# tenacity_pcb.net
KiCad netlist of a schematic drawn in EAGLE
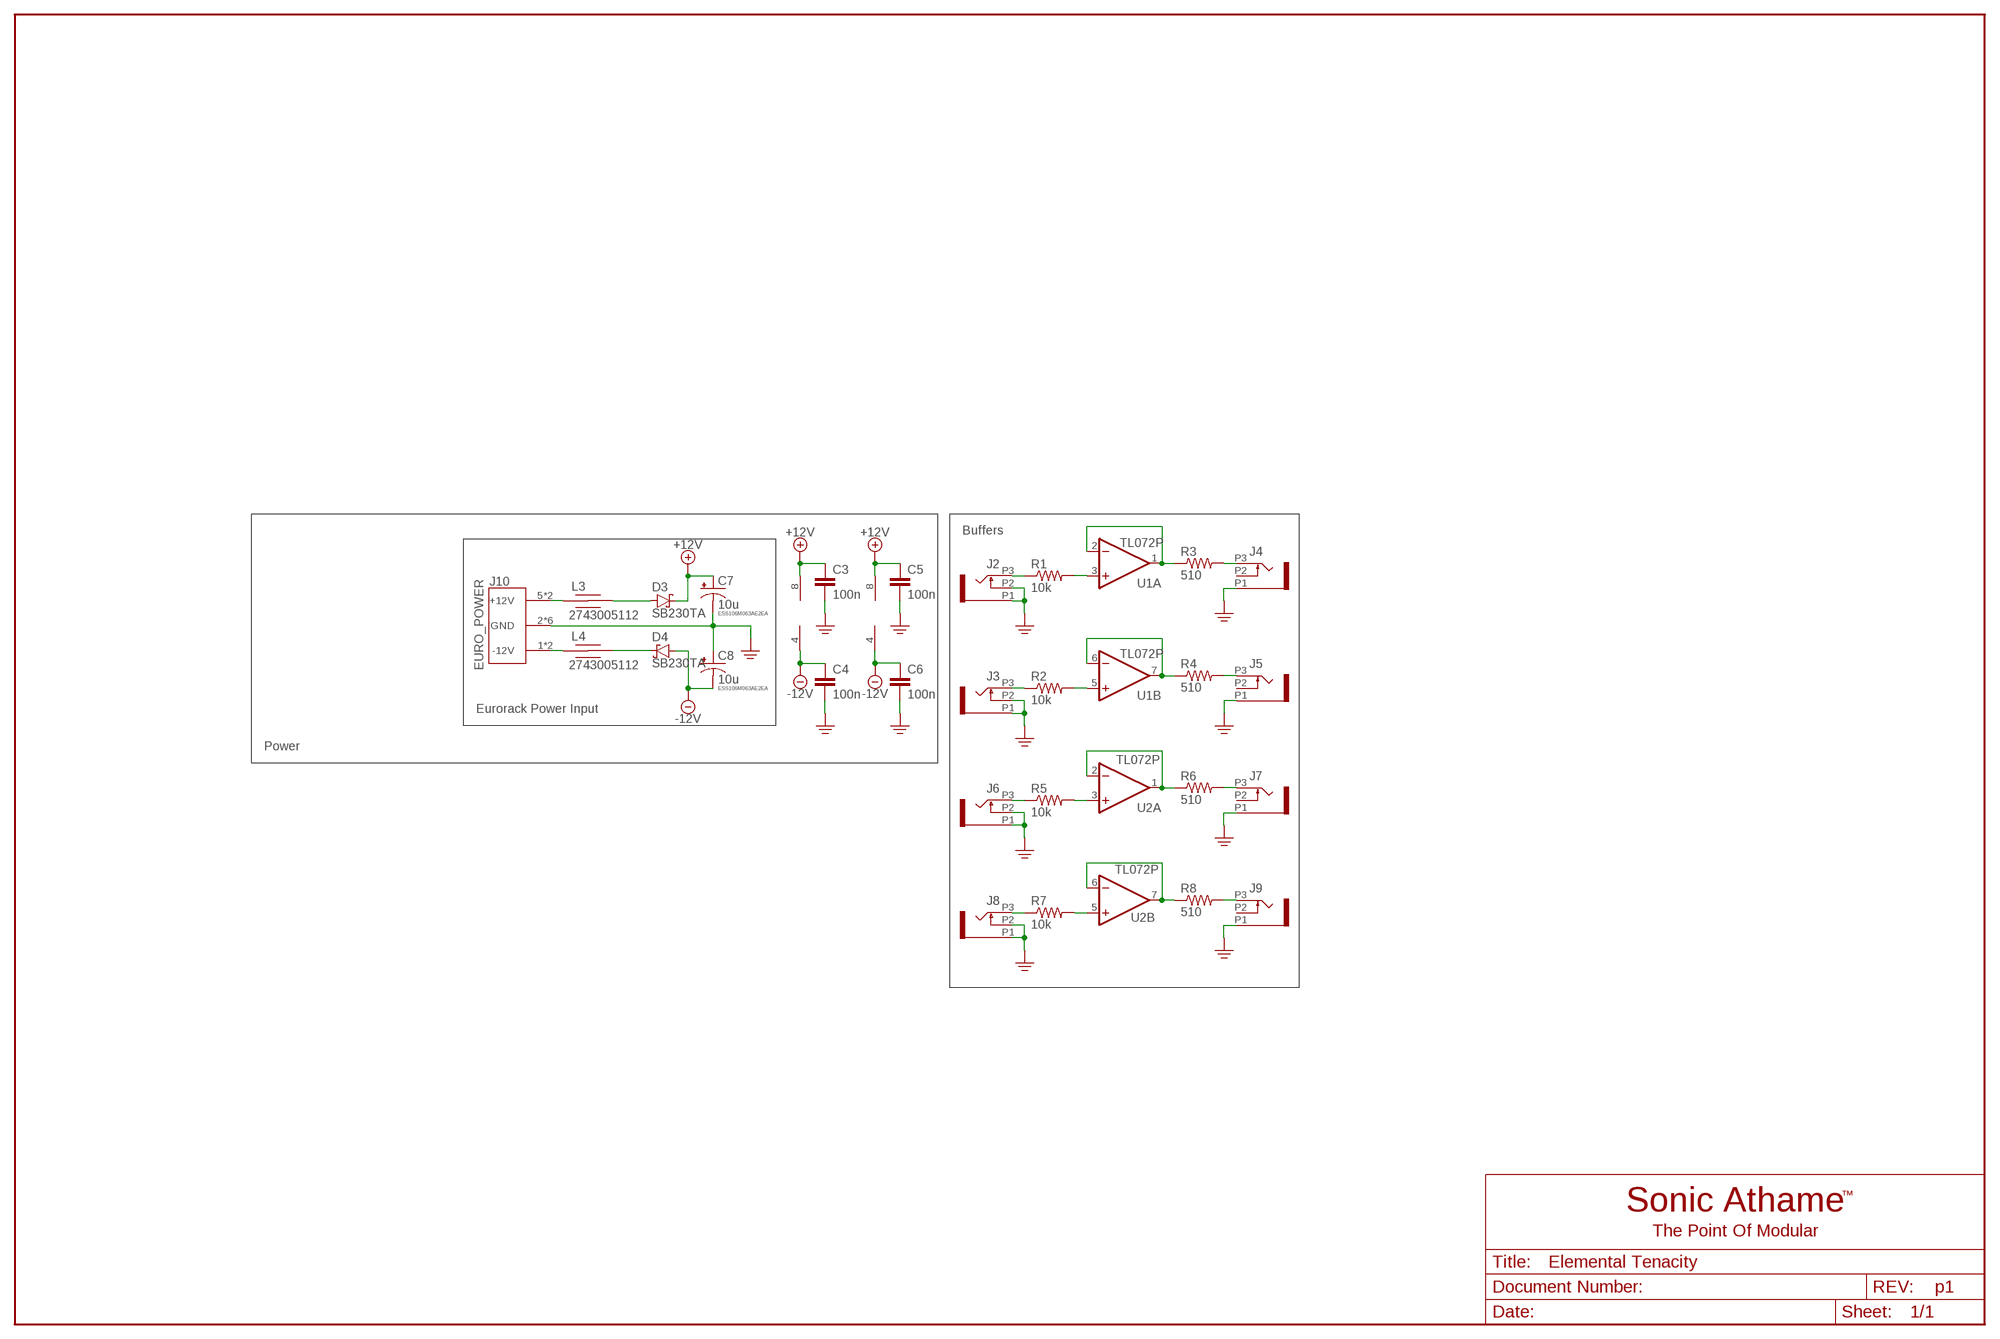
[diagram p0: schematic, sheet 1]

(export (version "E")
  (design (tool "Eeschema 10.0.6"))
  (components
    (comp (ref "C3")
      (value "100n")
      (footprint "eagle-import:C025-024X044")
      (libsource (lib "eagle-import") (part "CAP_NONPOL025-024X044"))
    )
    (comp (ref "C4")
      (value "100n")
      (footprint "eagle-import:C025-024X044")
      (libsource (lib "eagle-import") (part "CAP_NONPOL025-024X044"))
    )
    (comp (ref "C5")
      (value "100n")
      (footprint "eagle-import:C025-024X044")
      (libsource (lib "eagle-import") (part "CAP_NONPOL025-024X044"))
    )
    (comp (ref "C6")
      (value "100n")
      (footprint "eagle-import:C025-024X044")
      (libsource (lib "eagle-import") (part "CAP_NONPOL025-024X044"))
    )
    (comp (ref "C7")
      (value "10u")
      (footprint "eagle-import:TT2D5")
      (libsource (lib "eagle-import") (part "CAP_POLLYTIC_V"))
    )
    (comp (ref "C8")
      (value "10u")
      (footprint "eagle-import:TT2D5")
      (libsource (lib "eagle-import") (part "CAP_POLLYTIC_V"))
    )
    (comp (ref "D3")
      (value "SB230TA")
      (footprint "eagle-import:0207_2V-POL")
      (libsource (lib "eagle-import") (part "SCHOTTKY_THT"))
    )
    (comp (ref "D4")
      (value "SB230TA")
      (footprint "eagle-import:0207_2V-POL")
      (libsource (lib "eagle-import") (part "SCHOTTKY_THT"))
    )
    (comp (ref "J2")
      (value "WQP-PJ398SM6")
      (footprint "eagle-import:WQP_PJ_301M6")
      (libsource (lib "eagle-import") (part "WQP-PJ398SM6"))
    )
    (comp (ref "J3")
      (value "WQP-PJ398SM6")
      (footprint "eagle-import:WQP_PJ_301M6")
      (libsource (lib "eagle-import") (part "WQP-PJ398SM6"))
    )
    (comp (ref "J4")
      (value "WQP-PJ398SM6")
      (footprint "eagle-import:WQP_PJ_301M6")
      (libsource (lib "eagle-import") (part "WQP-PJ398SM6"))
    )
    (comp (ref "J5")
      (value "WQP-PJ398SM6")
      (footprint "eagle-import:WQP_PJ_301M6")
      (libsource (lib "eagle-import") (part "WQP-PJ398SM6"))
    )
    (comp (ref "J6")
      (value "WQP-PJ398SM6")
      (footprint "eagle-import:WQP_PJ_301M6")
      (libsource (lib "eagle-import") (part "WQP-PJ398SM6"))
    )
    (comp (ref "J7")
      (value "WQP-PJ398SM6")
      (footprint "eagle-import:WQP_PJ_301M6")
      (libsource (lib "eagle-import") (part "WQP-PJ398SM6"))
    )
    (comp (ref "J8")
      (value "WQP-PJ398SM6")
      (footprint "eagle-import:WQP_PJ_301M6")
      (libsource (lib "eagle-import") (part "WQP-PJ398SM6"))
    )
    (comp (ref "J9")
      (value "WQP-PJ398SM6")
      (footprint "eagle-import:WQP_PJ_301M6")
      (libsource (lib "eagle-import") (part "WQP-PJ398SM6"))
    )
    (comp (ref "J10")
      (value "EURO_POWER")
      (footprint "eagle-import:EURO_POWER")
      (libsource (lib "eagle-import") (part "EURO_POWER"))
    )
    (comp (ref "L3")
      (value "2743005112")
      (footprint "eagle-import:0207_2V")
      (libsource (lib "eagle-import") (part "FERRITE_THT"))
    )
    (comp (ref "L4")
      (value "2743005112")
      (footprint "eagle-import:0207_2V")
      (libsource (lib "eagle-import") (part "FERRITE_THT"))
    )
    (comp (ref "R1")
      (value "10k")
      (footprint "eagle-import:0207_2V")
      (libsource (lib "eagle-import") (part "RESISTOR0207/2V"))
    )
    (comp (ref "R2")
      (value "10k")
      (footprint "eagle-import:0207_2V")
      (libsource (lib "eagle-import") (part "RESISTOR0207/2V"))
    )
    (comp (ref "R3")
      (value "510")
      (footprint "eagle-import:0207_2V")
      (libsource (lib "eagle-import") (part "RESISTOR0207/2V"))
    )
    (comp (ref "R4")
      (value "510")
      (footprint "eagle-import:0207_2V")
      (libsource (lib "eagle-import") (part "RESISTOR0207/2V"))
    )
    (comp (ref "R5")
      (value "10k")
      (footprint "eagle-import:0207_2V")
      (libsource (lib "eagle-import") (part "RESISTOR0207/2V"))
    )
    (comp (ref "R6")
      (value "510")
      (footprint "eagle-import:0207_2V")
      (libsource (lib "eagle-import") (part "RESISTOR0207/2V"))
    )
    (comp (ref "R7")
      (value "10k")
      (footprint "eagle-import:0207_2V")
      (libsource (lib "eagle-import") (part "RESISTOR0207/2V"))
    )
    (comp (ref "R8")
      (value "510")
      (footprint "eagle-import:0207_2V")
      (libsource (lib "eagle-import") (part "RESISTOR0207/2V"))
    )
    (comp (ref "U1")
      (value "TL072P")
      (footprint "eagle-import:DIL08")
      (libsource (lib "eagle-import") (part "TL072P"))
    )
    (comp (ref "U2")
      (value "TL072P")
      (footprint "eagle-import:DIL08")
      (libsource (lib "eagle-import") (part "TL072P"))
    )
  )
  (nets
    (net (code "1") (name "+12V") (class "Default")
      (node (ref "C3") (pin "1") (pinfunction "1_1") (pintype "passive"))
      (node (ref "C5") (pin "1") (pinfunction "1_1") (pintype "passive"))
      (node (ref "C7") (pin "+") (pinfunction "+_+") (pintype "passive"))
      (node (ref "D3") (pin "C") (pinfunction "C_C") (pintype "passive"))
      (node (ref "U1") (pin "8") (pinfunction "V+_8") (pintype "power_in"))
      (node (ref "U2") (pin "8") (pinfunction "V+_8") (pintype "power_in"))
    )
    (net (code "2") (name "-12V") (class "Default")
      (node (ref "C4") (pin "1") (pinfunction "1_1") (pintype "passive"))
      (node (ref "C6") (pin "1") (pinfunction "1_1") (pintype "passive"))
      (node (ref "C8") (pin "-") (pinfunction "-_-") (pintype "passive"))
      (node (ref "D4") (pin "A") (pinfunction "A_A") (pintype "passive"))
      (node (ref "U1") (pin "4") (pinfunction "V-_4") (pintype "power_in"))
      (node (ref "U2") (pin "4") (pinfunction "V-_4") (pintype "power_in"))
    )
    (net (code "3") (name "GND") (class "Default")
      (node (ref "C3") (pin "2") (pinfunction "2_2") (pintype "passive"))
      (node (ref "C4") (pin "2") (pinfunction "2_2") (pintype "passive"))
      (node (ref "C5") (pin "2") (pinfunction "2_2") (pintype "passive"))
      (node (ref "C6") (pin "2") (pinfunction "2_2") (pintype "passive"))
      (node (ref "C7") (pin "-") (pinfunction "-_-") (pintype "passive"))
      (node (ref "C8") (pin "+") (pinfunction "+_+") (pintype "passive"))
      (node (ref "J10") (pin "2") (pinfunction "GND_2") (pintype "bidirectional"))
      (node (ref "J10") (pin "3") (pinfunction "GND_3") (pintype "bidirectional"))
      (node (ref "J10") (pin "4") (pinfunction "GND_4") (pintype "bidirectional"))
      (node (ref "J10") (pin "7") (pinfunction "GND_7") (pintype "bidirectional"))
      (node (ref "J10") (pin "8") (pinfunction "GND_8") (pintype "bidirectional"))
      (node (ref "J10") (pin "9") (pinfunction "GND_9") (pintype "bidirectional"))
      (node (ref "J2") (pin "P1") (pinfunction "1_P1") (pintype "passive"))
      (node (ref "J2") (pin "P2") (pinfunction "2_P2") (pintype "passive"))
      (node (ref "J3") (pin "P1") (pinfunction "1_P1") (pintype "passive"))
      (node (ref "J3") (pin "P2") (pinfunction "2_P2") (pintype "passive"))
      (node (ref "J4") (pin "P1") (pinfunction "1_P1") (pintype "passive"))
      (node (ref "J5") (pin "P1") (pinfunction "1_P1") (pintype "passive"))
      (node (ref "J6") (pin "P1") (pinfunction "1_P1") (pintype "passive"))
      (node (ref "J6") (pin "P2") (pinfunction "2_P2") (pintype "passive"))
      (node (ref "J7") (pin "P1") (pinfunction "1_P1") (pintype "passive"))
      (node (ref "J8") (pin "P1") (pinfunction "1_P1") (pintype "passive"))
      (node (ref "J8") (pin "P2") (pinfunction "2_P2") (pintype "passive"))
      (node (ref "J9") (pin "P1") (pinfunction "1_P1") (pintype "passive"))
    )
    (net (code "4") (name "Net-(J2-3)") (class "Default")
      (node (ref "J2") (pin "P3") (pinfunction "3_P3") (pintype "passive"))
      (node (ref "R1") (pin "1") (pinfunction "1_1") (pintype "passive"))
    )
    (net (code "5") (name "Net-(J3-3)") (class "Default")
      (node (ref "J3") (pin "P3") (pinfunction "3_P3") (pintype "passive"))
      (node (ref "R2") (pin "1") (pinfunction "1_1") (pintype "passive"))
    )
    (net (code "6") (name "Net-(J4-3)") (class "Default")
      (node (ref "J4") (pin "P3") (pinfunction "3_P3") (pintype "passive"))
      (node (ref "R3") (pin "2") (pinfunction "2_2") (pintype "passive"))
    )
    (net (code "7") (name "Net-(J5-3)") (class "Default")
      (node (ref "J5") (pin "P3") (pinfunction "3_P3") (pintype "passive"))
      (node (ref "R4") (pin "2") (pinfunction "2_2") (pintype "passive"))
    )
    (net (code "8") (name "Net-(J6-3)") (class "Default")
      (node (ref "J6") (pin "P3") (pinfunction "3_P3") (pintype "passive"))
      (node (ref "R5") (pin "1") (pinfunction "1_1") (pintype "passive"))
    )
    (net (code "9") (name "Net-(J7-3)") (class "Default")
      (node (ref "J7") (pin "P3") (pinfunction "3_P3") (pintype "passive"))
      (node (ref "R6") (pin "2") (pinfunction "2_2") (pintype "passive"))
    )
    (net (code "10") (name "Net-(J8-3)") (class "Default")
      (node (ref "J8") (pin "P3") (pinfunction "3_P3") (pintype "passive"))
      (node (ref "R7") (pin "1") (pinfunction "1_1") (pintype "passive"))
    )
    (net (code "11") (name "Net-(J9-3)") (class "Default")
      (node (ref "J9") (pin "P3") (pinfunction "3_P3") (pintype "passive"))
      (node (ref "R8") (pin "2") (pinfunction "2_2") (pintype "passive"))
    )
    (net (code "12") (name "Net-(L3-P$1)") (class "Default")
      (node (ref "J10") (pin "5") (pinfunction "+12V_5") (pintype "bidirectional"))
      (node (ref "J10") (pin "6") (pinfunction "+12V_6") (pintype "bidirectional"))
      (node (ref "L3") (pin "1") (pinfunction "P$1_1") (pintype "bidirectional"))
    )
    (net (code "13") (name "Net-(L3-P$2)") (class "Default")
      (node (ref "D3") (pin "A") (pinfunction "A_A") (pintype "passive"))
      (node (ref "L3") (pin "2") (pinfunction "P$2_2") (pintype "bidirectional"))
    )
    (net (code "14") (name "Net-(L4-P$1)") (class "Default")
      (node (ref "J10") (pin "1") (pinfunction "-12V_1") (pintype "bidirectional"))
      (node (ref "J10") (pin "10") (pinfunction "-12V_10") (pintype "bidirectional"))
      (node (ref "L4") (pin "1") (pinfunction "P$1_1") (pintype "bidirectional"))
    )
    (net (code "15") (name "Net-(L4-P$2)") (class "Default")
      (node (ref "D4") (pin "C") (pinfunction "C_C") (pintype "passive"))
      (node (ref "L4") (pin "2") (pinfunction "P$2_2") (pintype "bidirectional"))
    )
    (net (code "16") (name "Net-(U1A-+IN)") (class "Default")
      (node (ref "R1") (pin "2") (pinfunction "2_2") (pintype "passive"))
      (node (ref "U1") (pin "3") (pinfunction "+IN_3") (pintype "input"))
    )
    (net (code "17") (name "Net-(U1A--IN)") (class "Default")
      (node (ref "R3") (pin "1") (pinfunction "1_1") (pintype "passive"))
      (node (ref "U1") (pin "1") (pinfunction "OUT_1") (pintype "output"))
      (node (ref "U1") (pin "2") (pinfunction "-IN_2") (pintype "input"))
    )
    (net (code "18") (name "Net-(U1B-+IN)") (class "Default")
      (node (ref "R2") (pin "2") (pinfunction "2_2") (pintype "passive"))
      (node (ref "U1") (pin "5") (pinfunction "+IN_5") (pintype "input"))
    )
    (net (code "19") (name "Net-(U1B--IN)") (class "Default")
      (node (ref "R4") (pin "1") (pinfunction "1_1") (pintype "passive"))
      (node (ref "U1") (pin "6") (pinfunction "-IN_6") (pintype "input"))
      (node (ref "U1") (pin "7") (pinfunction "OUT_7") (pintype "output"))
    )
    (net (code "20") (name "Net-(U2A-+IN)") (class "Default")
      (node (ref "R5") (pin "2") (pinfunction "2_2") (pintype "passive"))
      (node (ref "U2") (pin "3") (pinfunction "+IN_3") (pintype "input"))
    )
    (net (code "21") (name "Net-(U2A--IN)") (class "Default")
      (node (ref "R6") (pin "1") (pinfunction "1_1") (pintype "passive"))
      (node (ref "U2") (pin "1") (pinfunction "OUT_1") (pintype "output"))
      (node (ref "U2") (pin "2") (pinfunction "-IN_2") (pintype "input"))
    )
    (net (code "22") (name "Net-(U2B-+IN)") (class "Default")
      (node (ref "R7") (pin "2") (pinfunction "2_2") (pintype "passive"))
      (node (ref "U2") (pin "5") (pinfunction "+IN_5") (pintype "input"))
    )
    (net (code "23") (name "Net-(U2B--IN)") (class "Default")
      (node (ref "R8") (pin "1") (pinfunction "1_1") (pintype "passive"))
      (node (ref "U2") (pin "6") (pinfunction "-IN_6") (pintype "input"))
      (node (ref "U2") (pin "7") (pinfunction "OUT_7") (pintype "output"))
    )
    (net (code "24") (name "unconnected-(J4-2-PadP2)") (class "Default")
      (node (ref "J4") (pin "P2") (pinfunction "2_P2") (pintype "passive"))
    )
    (net (code "25") (name "unconnected-(J5-2-PadP2)") (class "Default")
      (node (ref "J5") (pin "P2") (pinfunction "2_P2") (pintype "passive"))
    )
    (net (code "26") (name "unconnected-(J7-2-PadP2)") (class "Default")
      (node (ref "J7") (pin "P2") (pinfunction "2_P2") (pintype "passive"))
    )
    (net (code "27") (name "unconnected-(J9-2-PadP2)") (class "Default")
      (node (ref "J9") (pin "P2") (pinfunction "2_P2") (pintype "passive"))
    )
  )
)
